# LED.net
KiCad netlist of a schematic drawn in Altium Designer
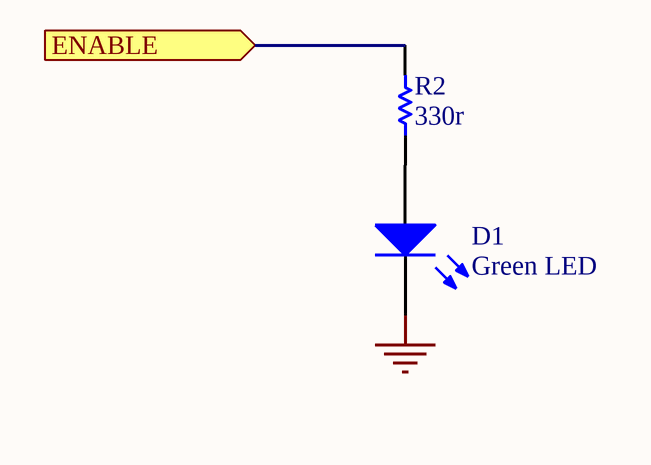
[diagram p0: LED.SchDoc]

(export (version "E")
  (design (tool "Eeschema 10.0.6"))
  (components
    (comp (ref "D1")
      (value "Green LED")
      (footprint "LED 0805")
      (description "Typical INFRARED GaAs LED")
      (libsource (lib "Miscellaneous Devices") (part "LED0"))
    )
    (comp (ref "R2")
      (value "330r")
      (footprint "RESC1608N")
      (description "Resistor")
      (fields (field (name "PUBLISHER") "Altium Limited"))
      (libsource (lib "Miscellaneous Devices") (part "Res1"))
    )
  )
  (nets
    (net (code "1") (name "/ENABLE") (class "Default")
      (node (ref "R2") (pin "2") (pinfunction "2_2") (pintype "passive"))
    )
    (net (code "2") (name "GND") (class "Default")
      (node (ref "D1") (pin "2") (pinfunction "K_2") (pintype "passive"))
    )
    (net (code "3") (name "Net-(D1-A)") (class "Default")
      (node (ref "D1") (pin "1") (pinfunction "A_1") (pintype "passive"))
      (node (ref "R2") (pin "1") (pinfunction "1_1") (pintype "passive"))
    )
  )
)
